# Bypass_FPGA_3V3.net
KiCad netlist of a schematic drawn in Altium Designer
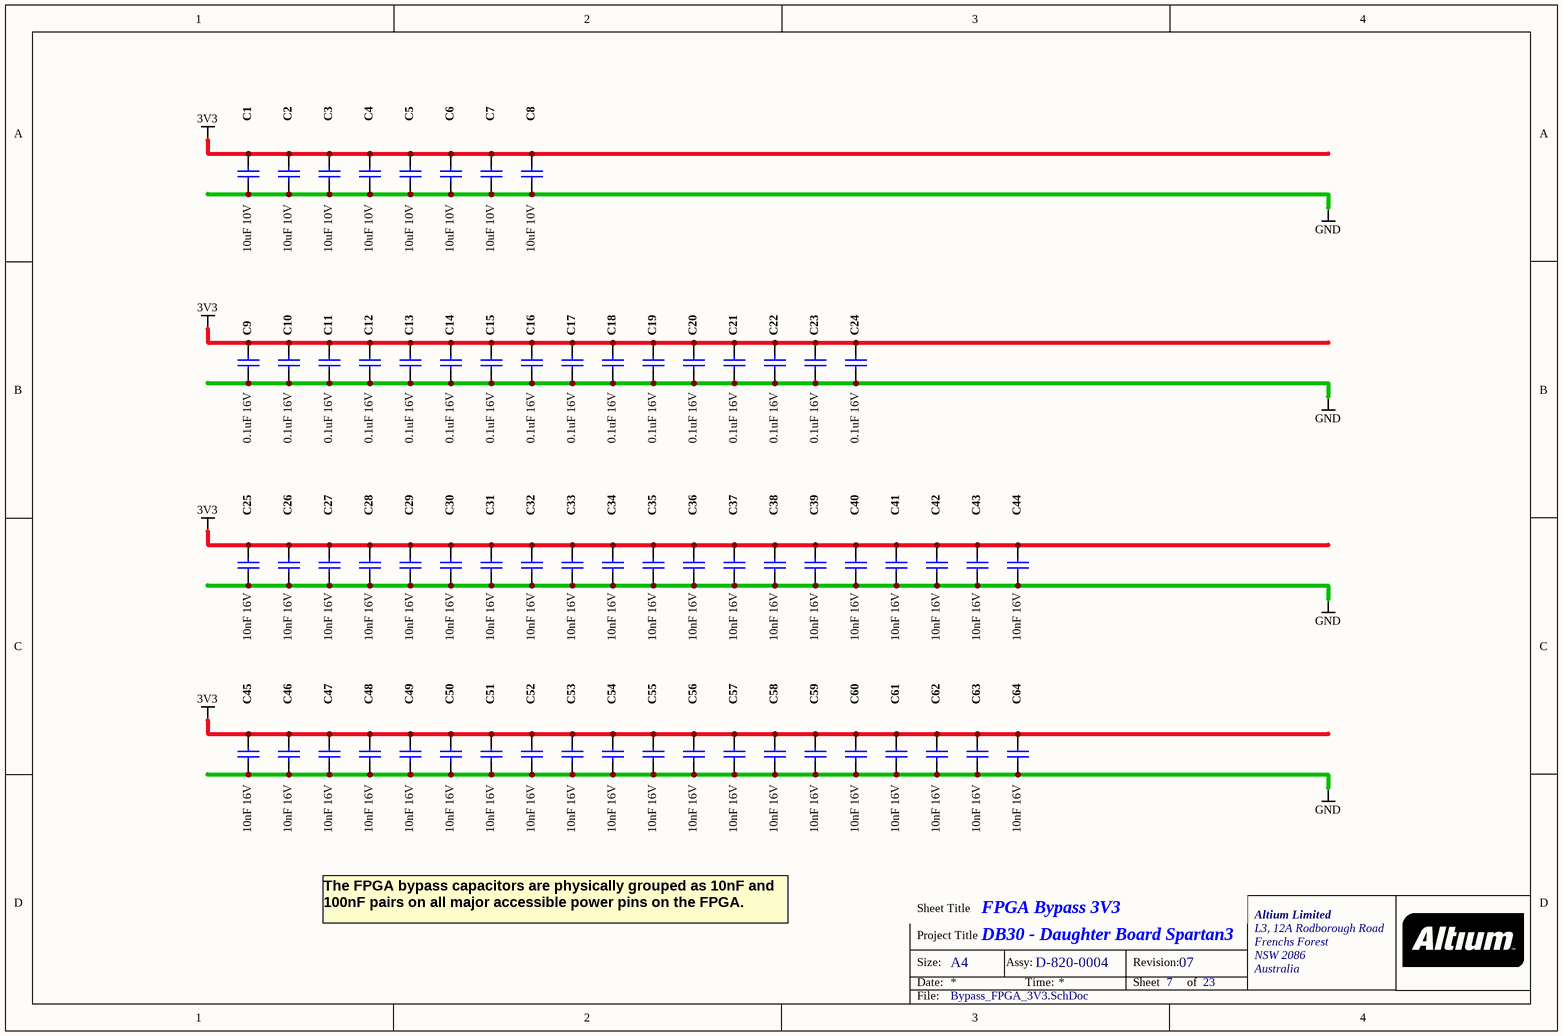
[diagram p0: Bypass_FPGA_3V3.SchDoc]

(export (version "E")
  (design (tool "Eeschema 10.0.6"))
  (components
    (comp (ref "C1")
      (value "10uF 10V")
      (footprint "CAPC2012-STAR")
      (description "Capacitor, Ceramic, 10uF 10% 10V 0805 (2012) X5R")
      (fields (field (name "TOLERANCE") "10 %"))
      (libsource (lib "AltiumDesignLibrary") (part "CAP-NP"))
    )
    (comp (ref "C2")
      (value "10uF 10V")
      (footprint "CAPC2012-STAR")
      (description "Capacitor, Ceramic, 10uF 10% 10V 0805 (2012) X5R")
      (fields (field (name "TOLERANCE") "10 %"))
      (libsource (lib "AltiumDesignLibrary") (part "CAP-NP"))
    )
    (comp (ref "C3")
      (value "10uF 10V")
      (footprint "CAPC2012-STAR")
      (description "Capacitor, Ceramic, 10uF 10% 10V 0805 (2012) X5R")
      (fields (field (name "TOLERANCE") "10 %"))
      (libsource (lib "AltiumDesignLibrary") (part "CAP-NP"))
    )
    (comp (ref "C4")
      (value "10uF 10V")
      (footprint "CAPC2012-STAR")
      (description "Capacitor, Ceramic, 10uF 10% 10V 0805 (2012) X5R")
      (fields (field (name "TOLERANCE") "10 %"))
      (libsource (lib "AltiumDesignLibrary") (part "CAP-NP"))
    )
    (comp (ref "C5")
      (value "10uF 10V")
      (footprint "CAPC2012-STAR")
      (description "Capacitor, Ceramic, 10uF 10% 10V 0805 (2012) X5R")
      (fields (field (name "TOLERANCE") "10 %"))
      (libsource (lib "AltiumDesignLibrary") (part "CAP-NP"))
    )
    (comp (ref "C6")
      (value "10uF 10V")
      (footprint "CAPC2012-STAR")
      (description "Capacitor, Ceramic, 10uF 10% 10V 0805 (2012) X5R")
      (fields (field (name "TOLERANCE") "10 %"))
      (libsource (lib "AltiumDesignLibrary") (part "CAP-NP"))
    )
    (comp (ref "C7")
      (value "10uF 10V")
      (footprint "CAPC2012-STAR")
      (description "Capacitor, Ceramic, 10uF 10% 10V 0805 (2012) X5R")
      (fields (field (name "TOLERANCE") "10 %"))
      (libsource (lib "AltiumDesignLibrary") (part "CAP-NP"))
    )
    (comp (ref "C8")
      (value "10uF 10V")
      (footprint "CAPC2012-STAR")
      (description "Capacitor, Ceramic, 10uF 10% 10V 0805 (2012) X5R")
      (fields (field (name "TOLERANCE") "10 %"))
      (libsource (lib "AltiumDesignLibrary") (part "CAP-NP"))
    )
    (comp (ref "C9")
      (value "0.1uF 16V")
      (footprint "CAPC1005-STAR")
      (description "Capacitor, Ceramic, 0.1uF 10% 16V 0402 (1005) X7R")
      (fields (field (name "TOLERANCE") "10 %"))
      (libsource (lib "altium-import") (part "root_0_mirrored_CAP-NP_"))
    )
    (comp (ref "C10")
      (value "0.1uF 16V")
      (footprint "CAPC1005-STAR")
      (description "Capacitor, Ceramic, 0.1uF 10% 16V 0402 (1005) X7R")
      (fields (field (name "TOLERANCE") "10 %"))
      (libsource (lib "altium-import") (part "root_0_mirrored_CAP-NP_"))
    )
    (comp (ref "C11")
      (value "0.1uF 16V")
      (footprint "CAPC1005-STAR")
      (description "Capacitor, Ceramic, 0.1uF 10% 16V 0402 (1005) X7R")
      (fields (field (name "TOLERANCE") "10 %"))
      (libsource (lib "altium-import") (part "root_0_mirrored_CAP-NP_"))
    )
    (comp (ref "C12")
      (value "0.1uF 16V")
      (footprint "CAPC1005-STAR")
      (description "Capacitor, Ceramic, 0.1uF 10% 16V 0402 (1005) X7R")
      (fields (field (name "TOLERANCE") "10 %"))
      (libsource (lib "altium-import") (part "root_0_mirrored_CAP-NP_"))
    )
    (comp (ref "C13")
      (value "0.1uF 16V")
      (footprint "CAPC1005-STAR")
      (description "Capacitor, Ceramic, 0.1uF 10% 16V 0402 (1005) X7R")
      (fields (field (name "TOLERANCE") "10 %"))
      (libsource (lib "altium-import") (part "root_0_mirrored_CAP-NP_"))
    )
    (comp (ref "C14")
      (value "0.1uF 16V")
      (footprint "CAPC1005-STAR")
      (description "Capacitor, Ceramic, 0.1uF 10% 16V 0402 (1005) X7R")
      (fields (field (name "TOLERANCE") "10 %"))
      (libsource (lib "altium-import") (part "root_0_mirrored_CAP-NP_"))
    )
    (comp (ref "C15")
      (value "0.1uF 16V")
      (footprint "CAPC1005-STAR")
      (description "Capacitor, Ceramic, 0.1uF 10% 16V 0402 (1005) X7R")
      (fields (field (name "TOLERANCE") "10 %"))
      (libsource (lib "altium-import") (part "root_0_mirrored_CAP-NP_"))
    )
    (comp (ref "C16")
      (value "0.1uF 16V")
      (footprint "CAPC1005-STAR")
      (description "Capacitor, Ceramic, 0.1uF 10% 16V 0402 (1005) X7R")
      (fields (field (name "TOLERANCE") "10 %"))
      (libsource (lib "altium-import") (part "root_0_mirrored_CAP-NP_"))
    )
    (comp (ref "C17")
      (value "0.1uF 16V")
      (footprint "CAPC1005-STAR")
      (description "Capacitor, Ceramic, 0.1uF 10% 16V 0402 (1005) X7R")
      (fields (field (name "TOLERANCE") "10 %"))
      (libsource (lib "altium-import") (part "root_0_mirrored_CAP-NP_"))
    )
    (comp (ref "C18")
      (value "0.1uF 16V")
      (footprint "CAPC1005-STAR")
      (description "Capacitor, Ceramic, 0.1uF 10% 16V 0402 (1005) X7R")
      (fields (field (name "TOLERANCE") "10 %"))
      (libsource (lib "altium-import") (part "root_0_mirrored_CAP-NP_"))
    )
    (comp (ref "C19")
      (value "0.1uF 16V")
      (footprint "CAPC1005-STAR")
      (description "Capacitor, Ceramic, 0.1uF 10% 16V 0402 (1005) X7R")
      (fields (field (name "TOLERANCE") "10 %"))
      (libsource (lib "altium-import") (part "root_0_mirrored_CAP-NP_"))
    )
    (comp (ref "C20")
      (value "0.1uF 16V")
      (footprint "CAPC1005-STAR")
      (description "Capacitor, Ceramic, 0.1uF 10% 16V 0402 (1005) X7R")
      (fields (field (name "TOLERANCE") "10 %"))
      (libsource (lib "altium-import") (part "root_0_mirrored_CAP-NP_"))
    )
    (comp (ref "C21")
      (value "0.1uF 16V")
      (footprint "CAPC1005-STAR")
      (description "Capacitor, Ceramic, 0.1uF 10% 16V 0402 (1005) X7R")
      (fields (field (name "TOLERANCE") "10 %"))
      (libsource (lib "altium-import") (part "root_0_mirrored_CAP-NP_"))
    )
    (comp (ref "C22")
      (value "0.1uF 16V")
      (footprint "CAPC1005-STAR")
      (description "Capacitor, Ceramic, 0.1uF 10% 16V 0402 (1005) X7R")
      (fields (field (name "TOLERANCE") "10 %"))
      (libsource (lib "altium-import") (part "root_0_mirrored_CAP-NP_"))
    )
    (comp (ref "C23")
      (value "0.1uF 16V")
      (footprint "CAPC1005-STAR")
      (description "Capacitor, Ceramic, 0.1uF 10% 16V 0402 (1005) X7R")
      (fields (field (name "TOLERANCE") "10 %"))
      (libsource (lib "altium-import") (part "root_0_mirrored_CAP-NP_"))
    )
    (comp (ref "C24")
      (value "0.1uF 16V")
      (footprint "CAPC1005-STAR")
      (description "Capacitor, Ceramic, 0.1uF 10% 16V 0402 (1005) X7R")
      (fields (field (name "TOLERANCE") "10 %"))
      (libsource (lib "altium-import") (part "root_0_mirrored_CAP-NP_"))
    )
    (comp (ref "C25")
      (value "10nF 16V")
      (footprint "CAPC1005-STAR")
      (description "Capacitor, Ceramic, 10nF 10% 16V 0402 (1005) X7R")
      (fields (field (name "TOLERANCE") "10 %"))
      (libsource (lib "altium-import") (part "root_0_CAP-NP_"))
    )
    (comp (ref "C26")
      (value "10nF 16V")
      (footprint "CAPC1005-STAR")
      (description "Capacitor, Ceramic, 10nF 10% 16V 0402 (1005) X7R")
      (fields (field (name "TOLERANCE") "10 %"))
      (libsource (lib "altium-import") (part "root_0_CAP-NP_"))
    )
    (comp (ref "C27")
      (value "10nF 16V")
      (footprint "CAPC1005-STAR")
      (description "Capacitor, Ceramic, 10nF 10% 16V 0402 (1005) X7R")
      (fields (field (name "TOLERANCE") "10 %"))
      (libsource (lib "altium-import") (part "root_0_CAP-NP_"))
    )
    (comp (ref "C28")
      (value "10nF 16V")
      (footprint "CAPC1005-STAR")
      (description "Capacitor, Ceramic, 10nF 10% 16V 0402 (1005) X7R")
      (fields (field (name "TOLERANCE") "10 %"))
      (libsource (lib "altium-import") (part "root_0_CAP-NP_"))
    )
    (comp (ref "C29")
      (value "10nF 16V")
      (footprint "CAPC1005-STAR")
      (description "Capacitor, Ceramic, 10nF 10% 16V 0402 (1005) X7R")
      (fields (field (name "TOLERANCE") "10 %"))
      (libsource (lib "altium-import") (part "root_0_CAP-NP_"))
    )
    (comp (ref "C30")
      (value "10nF 16V")
      (footprint "CAPC1005-STAR")
      (description "Capacitor, Ceramic, 10nF 10% 16V 0402 (1005) X7R")
      (fields (field (name "TOLERANCE") "10 %"))
      (libsource (lib "altium-import") (part "root_0_CAP-NP_"))
    )
    (comp (ref "C31")
      (value "10nF 16V")
      (footprint "CAPC1005-STAR")
      (description "Capacitor, Ceramic, 10nF 10% 16V 0402 (1005) X7R")
      (fields (field (name "TOLERANCE") "10 %"))
      (libsource (lib "altium-import") (part "root_0_CAP-NP_"))
    )
    (comp (ref "C32")
      (value "10nF 16V")
      (footprint "CAPC1005-STAR")
      (description "Capacitor, Ceramic, 10nF 10% 16V 0402 (1005) X7R")
      (fields (field (name "TOLERANCE") "10 %"))
      (libsource (lib "altium-import") (part "root_0_CAP-NP_"))
    )
    (comp (ref "C33")
      (value "10nF 16V")
      (footprint "CAPC1005-STAR")
      (description "Capacitor, Ceramic, 10nF 10% 16V 0402 (1005) X7R")
      (fields (field (name "TOLERANCE") "10 %"))
      (libsource (lib "altium-import") (part "root_0_CAP-NP_"))
    )
    (comp (ref "C34")
      (value "10nF 16V")
      (footprint "CAPC1005-STAR")
      (description "Capacitor, Ceramic, 10nF 10% 16V 0402 (1005) X7R")
      (fields (field (name "TOLERANCE") "10 %"))
      (libsource (lib "altium-import") (part "root_0_CAP-NP_"))
    )
    (comp (ref "C35")
      (value "10nF 16V")
      (footprint "CAPC1005-STAR")
      (description "Capacitor, Ceramic, 10nF 10% 16V 0402 (1005) X7R")
      (fields (field (name "TOLERANCE") "10 %"))
      (libsource (lib "altium-import") (part "root_0_CAP-NP_"))
    )
    (comp (ref "C36")
      (value "10nF 16V")
      (footprint "CAPC1005-STAR")
      (description "Capacitor, Ceramic, 10nF 10% 16V 0402 (1005) X7R")
      (fields (field (name "TOLERANCE") "10 %"))
      (libsource (lib "altium-import") (part "root_0_CAP-NP_"))
    )
    (comp (ref "C37")
      (value "10nF 16V")
      (footprint "CAPC1005-STAR")
      (description "Capacitor, Ceramic, 10nF 10% 16V 0402 (1005) X7R")
      (fields (field (name "TOLERANCE") "10 %"))
      (libsource (lib "altium-import") (part "root_0_CAP-NP_"))
    )
    (comp (ref "C38")
      (value "10nF 16V")
      (footprint "CAPC1005-STAR")
      (description "Capacitor, Ceramic, 10nF 10% 16V 0402 (1005) X7R")
      (fields (field (name "TOLERANCE") "10 %"))
      (libsource (lib "altium-import") (part "root_0_CAP-NP_"))
    )
    (comp (ref "C39")
      (value "10nF 16V")
      (footprint "CAPC1005-STAR")
      (description "Capacitor, Ceramic, 10nF 10% 16V 0402 (1005) X7R")
      (fields (field (name "TOLERANCE") "10 %"))
      (libsource (lib "altium-import") (part "root_0_CAP-NP_"))
    )
    (comp (ref "C40")
      (value "10nF 16V")
      (footprint "CAPC1005-STAR")
      (description "Capacitor, Ceramic, 10nF 10% 16V 0402 (1005) X7R")
      (fields (field (name "TOLERANCE") "10 %"))
      (libsource (lib "altium-import") (part "root_0_CAP-NP_"))
    )
    (comp (ref "C41")
      (value "10nF 16V")
      (footprint "CAPC1005-STAR")
      (description "Capacitor, Ceramic, 10nF 10% 16V 0402 (1005) X7R")
      (fields (field (name "TOLERANCE") "10 %"))
      (libsource (lib "altium-import") (part "root_0_CAP-NP_"))
    )
    (comp (ref "C42")
      (value "10nF 16V")
      (footprint "CAPC1005-STAR")
      (description "Capacitor, Ceramic, 10nF 10% 16V 0402 (1005) X7R")
      (fields (field (name "TOLERANCE") "10 %"))
      (libsource (lib "altium-import") (part "root_0_CAP-NP_"))
    )
    (comp (ref "C43")
      (value "10nF 16V")
      (footprint "CAPC1005-STAR")
      (description "Capacitor, Ceramic, 10nF 10% 16V 0402 (1005) X7R")
      (fields (field (name "TOLERANCE") "10 %"))
      (libsource (lib "altium-import") (part "root_0_CAP-NP_"))
    )
    (comp (ref "C44")
      (value "10nF 16V")
      (footprint "CAPC1005-STAR")
      (description "Capacitor, Ceramic, 10nF 10% 16V 0402 (1005) X7R")
      (fields (field (name "TOLERANCE") "10 %"))
      (libsource (lib "altium-import") (part "root_0_CAP-NP_"))
    )
    (comp (ref "C45")
      (value "10nF 16V")
      (footprint "CAPC1005-STAR")
      (description "Capacitor, Ceramic, 10nF 10% 16V 0402 (1005) X7R")
      (fields (field (name "TOLERANCE") "10 %"))
      (libsource (lib "altium-import") (part "root_0_CAP-NP_"))
    )
    (comp (ref "C46")
      (value "10nF 16V")
      (footprint "CAPC1005-STAR")
      (description "Capacitor, Ceramic, 10nF 10% 16V 0402 (1005) X7R")
      (fields (field (name "TOLERANCE") "10 %"))
      (libsource (lib "altium-import") (part "root_0_CAP-NP_"))
    )
    (comp (ref "C47")
      (value "10nF 16V")
      (footprint "CAPC1005-STAR")
      (description "Capacitor, Ceramic, 10nF 10% 16V 0402 (1005) X7R")
      (fields (field (name "TOLERANCE") "10 %"))
      (libsource (lib "altium-import") (part "root_0_CAP-NP_"))
    )
    (comp (ref "C48")
      (value "10nF 16V")
      (footprint "CAPC1005-STAR")
      (description "Capacitor, Ceramic, 10nF 10% 16V 0402 (1005) X7R")
      (fields (field (name "TOLERANCE") "10 %"))
      (libsource (lib "altium-import") (part "root_0_CAP-NP_"))
    )
    (comp (ref "C49")
      (value "10nF 16V")
      (footprint "CAPC1005-STAR")
      (description "Capacitor, Ceramic, 10nF 10% 16V 0402 (1005) X7R")
      (fields (field (name "TOLERANCE") "10 %"))
      (libsource (lib "altium-import") (part "root_0_CAP-NP_"))
    )
    (comp (ref "C50")
      (value "10nF 16V")
      (footprint "CAPC1005-STAR")
      (description "Capacitor, Ceramic, 10nF 10% 16V 0402 (1005) X7R")
      (fields (field (name "TOLERANCE") "10 %"))
      (libsource (lib "altium-import") (part "root_0_CAP-NP_"))
    )
    (comp (ref "C51")
      (value "10nF 16V")
      (footprint "CAPC1005-STAR")
      (description "Capacitor, Ceramic, 10nF 10% 16V 0402 (1005) X7R")
      (fields (field (name "TOLERANCE") "10 %"))
      (libsource (lib "altium-import") (part "root_0_CAP-NP_"))
    )
    (comp (ref "C52")
      (value "10nF 16V")
      (footprint "CAPC1005-STAR")
      (description "Capacitor, Ceramic, 10nF 10% 16V 0402 (1005) X7R")
      (fields (field (name "TOLERANCE") "10 %"))
      (libsource (lib "altium-import") (part "root_0_CAP-NP_"))
    )
    (comp (ref "C53")
      (value "10nF 16V")
      (footprint "CAPC1005-STAR")
      (description "Capacitor, Ceramic, 10nF 10% 16V 0402 (1005) X7R")
      (fields (field (name "TOLERANCE") "10 %"))
      (libsource (lib "altium-import") (part "root_0_CAP-NP_"))
    )
    (comp (ref "C54")
      (value "10nF 16V")
      (footprint "CAPC1005-STAR")
      (description "Capacitor, Ceramic, 10nF 10% 16V 0402 (1005) X7R")
      (fields (field (name "TOLERANCE") "10 %"))
      (libsource (lib "altium-import") (part "root_0_CAP-NP_"))
    )
    (comp (ref "C55")
      (value "10nF 16V")
      (footprint "CAPC1005-STAR")
      (description "Capacitor, Ceramic, 10nF 10% 16V 0402 (1005) X7R")
      (fields (field (name "TOLERANCE") "10 %"))
      (libsource (lib "altium-import") (part "root_0_CAP-NP_"))
    )
    (comp (ref "C56")
      (value "10nF 16V")
      (footprint "CAPC1005-STAR")
      (description "Capacitor, Ceramic, 10nF 10% 16V 0402 (1005) X7R")
      (fields (field (name "TOLERANCE") "10 %"))
      (libsource (lib "altium-import") (part "root_0_CAP-NP_"))
    )
    (comp (ref "C57")
      (value "10nF 16V")
      (footprint "CAPC1005-STAR")
      (description "Capacitor, Ceramic, 10nF 10% 16V 0402 (1005) X7R")
      (fields (field (name "TOLERANCE") "10 %"))
      (libsource (lib "altium-import") (part "root_0_CAP-NP_"))
    )
    (comp (ref "C58")
      (value "10nF 16V")
      (footprint "CAPC1005-STAR")
      (description "Capacitor, Ceramic, 10nF 10% 16V 0402 (1005) X7R")
      (fields (field (name "TOLERANCE") "10 %"))
      (libsource (lib "altium-import") (part "root_0_CAP-NP_"))
    )
    (comp (ref "C59")
      (value "10nF 16V")
      (footprint "CAPC1005-STAR")
      (description "Capacitor, Ceramic, 10nF 10% 16V 0402 (1005) X7R")
      (fields (field (name "TOLERANCE") "10 %"))
      (libsource (lib "altium-import") (part "root_0_CAP-NP_"))
    )
    (comp (ref "C60")
      (value "10nF 16V")
      (footprint "CAPC1005-STAR")
      (description "Capacitor, Ceramic, 10nF 10% 16V 0402 (1005) X7R")
      (fields (field (name "TOLERANCE") "10 %"))
      (libsource (lib "altium-import") (part "root_0_CAP-NP_"))
    )
    (comp (ref "C61")
      (value "10nF 16V")
      (footprint "CAPC1005-STAR")
      (description "Capacitor, Ceramic, 10nF 10% 16V 0402 (1005) X7R")
      (fields (field (name "TOLERANCE") "10 %"))
      (libsource (lib "altium-import") (part "root_0_CAP-NP_"))
    )
    (comp (ref "C62")
      (value "10nF 16V")
      (footprint "CAPC1005-STAR")
      (description "Capacitor, Ceramic, 10nF 10% 16V 0402 (1005) X7R")
      (fields (field (name "TOLERANCE") "10 %"))
      (libsource (lib "altium-import") (part "root_0_CAP-NP_"))
    )
    (comp (ref "C63")
      (value "10nF 16V")
      (footprint "CAPC1005-STAR")
      (description "Capacitor, Ceramic, 10nF 10% 16V 0402 (1005) X7R")
      (fields (field (name "TOLERANCE") "10 %"))
      (libsource (lib "altium-import") (part "root_0_CAP-NP_"))
    )
    (comp (ref "C64")
      (value "10nF 16V")
      (footprint "CAPC1005-STAR")
      (description "Capacitor, Ceramic, 10nF 10% 16V 0402 (1005) X7R")
      (fields (field (name "TOLERANCE") "10 %"))
      (libsource (lib "altium-import") (part "root_0_CAP-NP_"))
    )
  )
  (nets
    (net (code "1") (name "3V3") (class "Default")
      (node (ref "C1") (pin "1") (pinfunction "1_1") (pintype "passive"))
      (node (ref "C10") (pin "1") (pinfunction "1_1") (pintype "passive"))
      (node (ref "C11") (pin "1") (pinfunction "1_1") (pintype "passive"))
      (node (ref "C12") (pin "1") (pinfunction "1_1") (pintype "passive"))
      (node (ref "C13") (pin "1") (pinfunction "1_1") (pintype "passive"))
      (node (ref "C14") (pin "1") (pinfunction "1_1") (pintype "passive"))
      (node (ref "C15") (pin "1") (pinfunction "1_1") (pintype "passive"))
      (node (ref "C16") (pin "1") (pinfunction "1_1") (pintype "passive"))
      (node (ref "C17") (pin "1") (pinfunction "1_1") (pintype "passive"))
      (node (ref "C18") (pin "1") (pinfunction "1_1") (pintype "passive"))
      (node (ref "C19") (pin "1") (pinfunction "1_1") (pintype "passive"))
      (node (ref "C2") (pin "1") (pinfunction "1_1") (pintype "passive"))
      (node (ref "C20") (pin "1") (pinfunction "1_1") (pintype "passive"))
      (node (ref "C21") (pin "1") (pinfunction "1_1") (pintype "passive"))
      (node (ref "C22") (pin "1") (pinfunction "1_1") (pintype "passive"))
      (node (ref "C23") (pin "1") (pinfunction "1_1") (pintype "passive"))
      (node (ref "C24") (pin "1") (pinfunction "1_1") (pintype "passive"))
      (node (ref "C25") (pin "1") (pinfunction "1_1") (pintype "passive"))
      (node (ref "C26") (pin "1") (pinfunction "1_1") (pintype "passive"))
      (node (ref "C27") (pin "1") (pinfunction "1_1") (pintype "passive"))
      (node (ref "C28") (pin "1") (pinfunction "1_1") (pintype "passive"))
      (node (ref "C29") (pin "1") (pinfunction "1_1") (pintype "passive"))
      (node (ref "C3") (pin "1") (pinfunction "1_1") (pintype "passive"))
      (node (ref "C30") (pin "1") (pinfunction "1_1") (pintype "passive"))
      (node (ref "C31") (pin "1") (pinfunction "1_1") (pintype "passive"))
      (node (ref "C32") (pin "1") (pinfunction "1_1") (pintype "passive"))
      (node (ref "C33") (pin "1") (pinfunction "1_1") (pintype "passive"))
      (node (ref "C34") (pin "1") (pinfunction "1_1") (pintype "passive"))
      (node (ref "C35") (pin "1") (pinfunction "1_1") (pintype "passive"))
      (node (ref "C36") (pin "1") (pinfunction "1_1") (pintype "passive"))
      (node (ref "C37") (pin "1") (pinfunction "1_1") (pintype "passive"))
      (node (ref "C38") (pin "1") (pinfunction "1_1") (pintype "passive"))
      (node (ref "C39") (pin "1") (pinfunction "1_1") (pintype "passive"))
      (node (ref "C4") (pin "1") (pinfunction "1_1") (pintype "passive"))
      (node (ref "C40") (pin "1") (pinfunction "1_1") (pintype "passive"))
      (node (ref "C41") (pin "1") (pinfunction "1_1") (pintype "passive"))
      (node (ref "C42") (pin "1") (pinfunction "1_1") (pintype "passive"))
      (node (ref "C43") (pin "1") (pinfunction "1_1") (pintype "passive"))
      (node (ref "C44") (pin "1") (pinfunction "1_1") (pintype "passive"))
      (node (ref "C45") (pin "1") (pinfunction "1_1") (pintype "passive"))
      (node (ref "C46") (pin "1") (pinfunction "1_1") (pintype "passive"))
      (node (ref "C47") (pin "1") (pinfunction "1_1") (pintype "passive"))
      (node (ref "C48") (pin "1") (pinfunction "1_1") (pintype "passive"))
      (node (ref "C49") (pin "1") (pinfunction "1_1") (pintype "passive"))
      (node (ref "C5") (pin "1") (pinfunction "1_1") (pintype "passive"))
      (node (ref "C50") (pin "1") (pinfunction "1_1") (pintype "passive"))
      (node (ref "C51") (pin "1") (pinfunction "1_1") (pintype "passive"))
      (node (ref "C52") (pin "1") (pinfunction "1_1") (pintype "passive"))
      (node (ref "C53") (pin "1") (pinfunction "1_1") (pintype "passive"))
      (node (ref "C54") (pin "1") (pinfunction "1_1") (pintype "passive"))
      (node (ref "C55") (pin "1") (pinfunction "1_1") (pintype "passive"))
      (node (ref "C56") (pin "1") (pinfunction "1_1") (pintype "passive"))
      (node (ref "C57") (pin "1") (pinfunction "1_1") (pintype "passive"))
      (node (ref "C58") (pin "1") (pinfunction "1_1") (pintype "passive"))
      (node (ref "C59") (pin "1") (pinfunction "1_1") (pintype "passive"))
      (node (ref "C6") (pin "1") (pinfunction "1_1") (pintype "passive"))
      (node (ref "C60") (pin "1") (pinfunction "1_1") (pintype "passive"))
      (node (ref "C61") (pin "1") (pinfunction "1_1") (pintype "passive"))
      (node (ref "C62") (pin "1") (pinfunction "1_1") (pintype "passive"))
      (node (ref "C63") (pin "1") (pinfunction "1_1") (pintype "passive"))
      (node (ref "C64") (pin "1") (pinfunction "1_1") (pintype "passive"))
      (node (ref "C7") (pin "1") (pinfunction "1_1") (pintype "passive"))
      (node (ref "C8") (pin "1") (pinfunction "1_1") (pintype "passive"))
      (node (ref "C9") (pin "1") (pinfunction "1_1") (pintype "passive"))
    )
    (net (code "2") (name "GND") (class "Default")
      (node (ref "C1") (pin "2") (pinfunction "2_2") (pintype "passive"))
      (node (ref "C10") (pin "2") (pinfunction "2_2") (pintype "passive"))
      (node (ref "C11") (pin "2") (pinfunction "2_2") (pintype "passive"))
      (node (ref "C12") (pin "2") (pinfunction "2_2") (pintype "passive"))
      (node (ref "C13") (pin "2") (pinfunction "2_2") (pintype "passive"))
      (node (ref "C14") (pin "2") (pinfunction "2_2") (pintype "passive"))
      (node (ref "C15") (pin "2") (pinfunction "2_2") (pintype "passive"))
      (node (ref "C16") (pin "2") (pinfunction "2_2") (pintype "passive"))
      (node (ref "C17") (pin "2") (pinfunction "2_2") (pintype "passive"))
      (node (ref "C18") (pin "2") (pinfunction "2_2") (pintype "passive"))
      (node (ref "C19") (pin "2") (pinfunction "2_2") (pintype "passive"))
      (node (ref "C2") (pin "2") (pinfunction "2_2") (pintype "passive"))
      (node (ref "C20") (pin "2") (pinfunction "2_2") (pintype "passive"))
      (node (ref "C21") (pin "2") (pinfunction "2_2") (pintype "passive"))
      (node (ref "C22") (pin "2") (pinfunction "2_2") (pintype "passive"))
      (node (ref "C23") (pin "2") (pinfunction "2_2") (pintype "passive"))
      (node (ref "C24") (pin "2") (pinfunction "2_2") (pintype "passive"))
      (node (ref "C25") (pin "2") (pinfunction "2_2") (pintype "passive"))
      (node (ref "C26") (pin "2") (pinfunction "2_2") (pintype "passive"))
      (node (ref "C27") (pin "2") (pinfunction "2_2") (pintype "passive"))
      (node (ref "C28") (pin "2") (pinfunction "2_2") (pintype "passive"))
      (node (ref "C29") (pin "2") (pinfunction "2_2") (pintype "passive"))
      (node (ref "C3") (pin "2") (pinfunction "2_2") (pintype "passive"))
      (node (ref "C30") (pin "2") (pinfunction "2_2") (pintype "passive"))
      (node (ref "C31") (pin "2") (pinfunction "2_2") (pintype "passive"))
      (node (ref "C32") (pin "2") (pinfunction "2_2") (pintype "passive"))
      (node (ref "C33") (pin "2") (pinfunction "2_2") (pintype "passive"))
      (node (ref "C34") (pin "2") (pinfunction "2_2") (pintype "passive"))
      (node (ref "C35") (pin "2") (pinfunction "2_2") (pintype "passive"))
      (node (ref "C36") (pin "2") (pinfunction "2_2") (pintype "passive"))
      (node (ref "C37") (pin "2") (pinfunction "2_2") (pintype "passive"))
      (node (ref "C38") (pin "2") (pinfunction "2_2") (pintype "passive"))
      (node (ref "C39") (pin "2") (pinfunction "2_2") (pintype "passive"))
      (node (ref "C4") (pin "2") (pinfunction "2_2") (pintype "passive"))
      (node (ref "C40") (pin "2") (pinfunction "2_2") (pintype "passive"))
      (node (ref "C41") (pin "2") (pinfunction "2_2") (pintype "passive"))
      (node (ref "C42") (pin "2") (pinfunction "2_2") (pintype "passive"))
      (node (ref "C43") (pin "2") (pinfunction "2_2") (pintype "passive"))
      (node (ref "C44") (pin "2") (pinfunction "2_2") (pintype "passive"))
      (node (ref "C45") (pin "2") (pinfunction "2_2") (pintype "passive"))
      (node (ref "C46") (pin "2") (pinfunction "2_2") (pintype "passive"))
      (node (ref "C47") (pin "2") (pinfunction "2_2") (pintype "passive"))
      (node (ref "C48") (pin "2") (pinfunction "2_2") (pintype "passive"))
      (node (ref "C49") (pin "2") (pinfunction "2_2") (pintype "passive"))
      (node (ref "C5") (pin "2") (pinfunction "2_2") (pintype "passive"))
      (node (ref "C50") (pin "2") (pinfunction "2_2") (pintype "passive"))
      (node (ref "C51") (pin "2") (pinfunction "2_2") (pintype "passive"))
      (node (ref "C52") (pin "2") (pinfunction "2_2") (pintype "passive"))
      (node (ref "C53") (pin "2") (pinfunction "2_2") (pintype "passive"))
      (node (ref "C54") (pin "2") (pinfunction "2_2") (pintype "passive"))
      (node (ref "C55") (pin "2") (pinfunction "2_2") (pintype "passive"))
      (node (ref "C56") (pin "2") (pinfunction "2_2") (pintype "passive"))
      (node (ref "C57") (pin "2") (pinfunction "2_2") (pintype "passive"))
      (node (ref "C58") (pin "2") (pinfunction "2_2") (pintype "passive"))
      (node (ref "C59") (pin "2") (pinfunction "2_2") (pintype "passive"))
      (node (ref "C6") (pin "2") (pinfunction "2_2") (pintype "passive"))
      (node (ref "C60") (pin "2") (pinfunction "2_2") (pintype "passive"))
      (node (ref "C61") (pin "2") (pinfunction "2_2") (pintype "passive"))
      (node (ref "C62") (pin "2") (pinfunction "2_2") (pintype "passive"))
      (node (ref "C63") (pin "2") (pinfunction "2_2") (pintype "passive"))
      (node (ref "C64") (pin "2") (pinfunction "2_2") (pintype "passive"))
      (node (ref "C7") (pin "2") (pinfunction "2_2") (pintype "passive"))
      (node (ref "C8") (pin "2") (pinfunction "2_2") (pintype "passive"))
      (node (ref "C9") (pin "2") (pinfunction "2_2") (pintype "passive"))
    )
  )
)
